# lcd20x4_keyboard.net
KiCad netlist of a schematic drawn in EAGLE
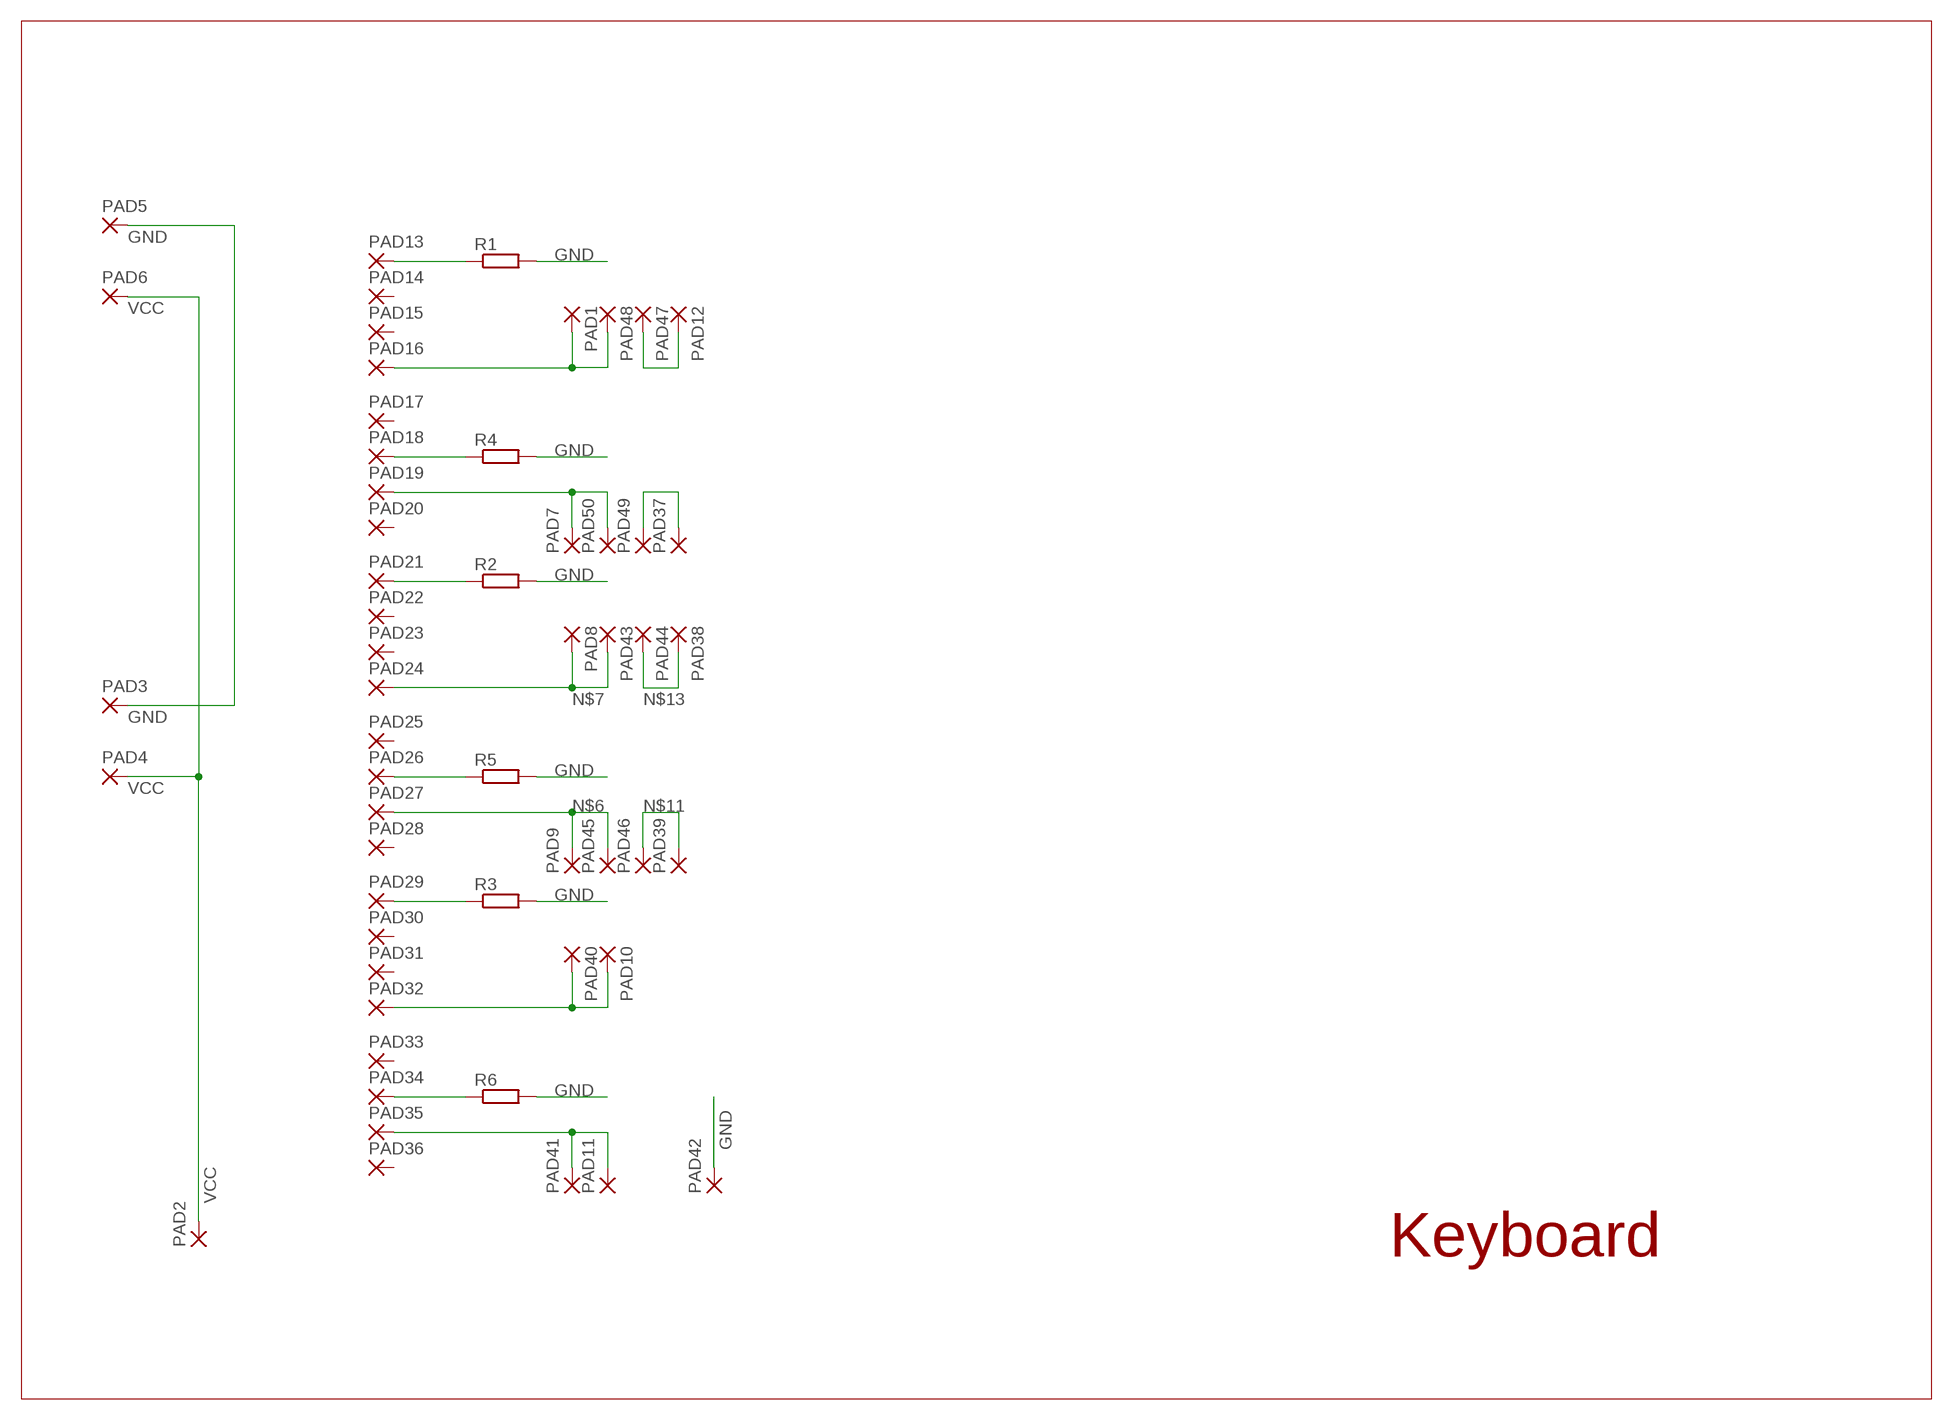
[diagram p0: schematic, sheet 1]

(export (version "E")
  (design (tool "Eeschema 10.0.6"))
  (components
    (comp (ref "PAD1")
      (value "WIREPAD1,6/0,8")
      (footprint "eagle-import:1,6_0,8")
      (libsource (lib "eagle-import") (part "WIREPAD1,6/0,8"))
    )
    (comp (ref "PAD2")
      (value "WIREPAD1,6/0,8")
      (footprint "eagle-import:1,6_0,8")
      (libsource (lib "eagle-import") (part "WIREPAD1,6/0,8"))
    )
    (comp (ref "PAD3")
      (value "WIREPAD1,6/0,8")
      (footprint "eagle-import:1,6_0,8")
      (libsource (lib "eagle-import") (part "WIREPAD1,6/0,8"))
    )
    (comp (ref "PAD4")
      (value "WIREPAD1,6/0,8")
      (footprint "eagle-import:1,6_0,8")
      (libsource (lib "eagle-import") (part "WIREPAD1,6/0,8"))
    )
    (comp (ref "PAD5")
      (value "WIREPAD1,6/0,8")
      (footprint "eagle-import:1,6_0,8")
      (libsource (lib "eagle-import") (part "WIREPAD1,6/0,8"))
    )
    (comp (ref "PAD6")
      (value "WIREPAD1,6/0,8")
      (footprint "eagle-import:1,6_0,8")
      (libsource (lib "eagle-import") (part "WIREPAD1,6/0,8"))
    )
    (comp (ref "PAD7")
      (value "WIREPAD1,6/0,8")
      (footprint "eagle-import:1,6_0,8")
      (libsource (lib "eagle-import") (part "WIREPAD1,6/0,8"))
    )
    (comp (ref "PAD8")
      (value "WIREPAD1,6/0,8")
      (footprint "eagle-import:1,6_0,8")
      (libsource (lib "eagle-import") (part "WIREPAD1,6/0,8"))
    )
    (comp (ref "PAD9")
      (value "WIREPAD1,6/0,8")
      (footprint "eagle-import:1,6_0,8")
      (libsource (lib "eagle-import") (part "WIREPAD1,6/0,8"))
    )
    (comp (ref "PAD10")
      (value "WIREPAD1,6/0,8")
      (footprint "eagle-import:1,6_0,8")
      (libsource (lib "eagle-import") (part "WIREPAD1,6/0,8"))
    )
    (comp (ref "PAD11")
      (value "WIREPAD1,6/0,8")
      (footprint "eagle-import:1,6_0,8")
      (libsource (lib "eagle-import") (part "WIREPAD1,6/0,8"))
    )
    (comp (ref "PAD12")
      (value "WIREPAD1,6/0,8")
      (footprint "eagle-import:1,6_0,8")
      (libsource (lib "eagle-import") (part "WIREPAD1,6/0,8"))
    )
    (comp (ref "PAD13")
      (value "WIREPAD1,6/0,8")
      (footprint "eagle-import:1,6_0,8")
      (libsource (lib "eagle-import") (part "WIREPAD1,6/0,8"))
    )
    (comp (ref "PAD14")
      (value "WIREPAD1,6/0,8")
      (footprint "eagle-import:1,6_0,8")
      (libsource (lib "eagle-import") (part "WIREPAD1,6/0,8"))
    )
    (comp (ref "PAD15")
      (value "WIREPAD1,6/0,8")
      (footprint "eagle-import:1,6_0,8")
      (libsource (lib "eagle-import") (part "WIREPAD1,6/0,8"))
    )
    (comp (ref "PAD16")
      (value "WIREPAD1,6/0,8")
      (footprint "eagle-import:1,6_0,8")
      (libsource (lib "eagle-import") (part "WIREPAD1,6/0,8"))
    )
    (comp (ref "PAD17")
      (value "WIREPAD1,6/0,8")
      (footprint "eagle-import:1,6_0,8")
      (libsource (lib "eagle-import") (part "WIREPAD1,6/0,8"))
    )
    (comp (ref "PAD18")
      (value "WIREPAD1,6/0,8")
      (footprint "eagle-import:1,6_0,8")
      (libsource (lib "eagle-import") (part "WIREPAD1,6/0,8"))
    )
    (comp (ref "PAD19")
      (value "WIREPAD1,6/0,8")
      (footprint "eagle-import:1,6_0,8")
      (libsource (lib "eagle-import") (part "WIREPAD1,6/0,8"))
    )
    (comp (ref "PAD20")
      (value "WIREPAD1,6/0,8")
      (footprint "eagle-import:1,6_0,8")
      (libsource (lib "eagle-import") (part "WIREPAD1,6/0,8"))
    )
    (comp (ref "PAD21")
      (value "WIREPAD1,6/0,8")
      (footprint "eagle-import:1,6_0,8")
      (libsource (lib "eagle-import") (part "WIREPAD1,6/0,8"))
    )
    (comp (ref "PAD22")
      (value "WIREPAD1,6/0,8")
      (footprint "eagle-import:1,6_0,8")
      (libsource (lib "eagle-import") (part "WIREPAD1,6/0,8"))
    )
    (comp (ref "PAD23")
      (value "WIREPAD1,6/0,8")
      (footprint "eagle-import:1,6_0,8")
      (libsource (lib "eagle-import") (part "WIREPAD1,6/0,8"))
    )
    (comp (ref "PAD24")
      (value "WIREPAD1,6/0,8")
      (footprint "eagle-import:1,6_0,8")
      (libsource (lib "eagle-import") (part "WIREPAD1,6/0,8"))
    )
    (comp (ref "PAD25")
      (value "WIREPAD1,6/0,8")
      (footprint "eagle-import:1,6_0,8")
      (libsource (lib "eagle-import") (part "WIREPAD1,6/0,8"))
    )
    (comp (ref "PAD26")
      (value "WIREPAD1,6/0,8")
      (footprint "eagle-import:1,6_0,8")
      (libsource (lib "eagle-import") (part "WIREPAD1,6/0,8"))
    )
    (comp (ref "PAD27")
      (value "WIREPAD1,6/0,8")
      (footprint "eagle-import:1,6_0,8")
      (libsource (lib "eagle-import") (part "WIREPAD1,6/0,8"))
    )
    (comp (ref "PAD28")
      (value "WIREPAD1,6/0,8")
      (footprint "eagle-import:1,6_0,8")
      (libsource (lib "eagle-import") (part "WIREPAD1,6/0,8"))
    )
    (comp (ref "PAD29")
      (value "WIREPAD1,6/0,8")
      (footprint "eagle-import:1,6_0,8")
      (libsource (lib "eagle-import") (part "WIREPAD1,6/0,8"))
    )
    (comp (ref "PAD30")
      (value "WIREPAD1,6/0,8")
      (footprint "eagle-import:1,6_0,8")
      (libsource (lib "eagle-import") (part "WIREPAD1,6/0,8"))
    )
    (comp (ref "PAD31")
      (value "WIREPAD1,6/0,8")
      (footprint "eagle-import:1,6_0,8")
      (libsource (lib "eagle-import") (part "WIREPAD1,6/0,8"))
    )
    (comp (ref "PAD32")
      (value "WIREPAD1,6/0,8")
      (footprint "eagle-import:1,6_0,8")
      (libsource (lib "eagle-import") (part "WIREPAD1,6/0,8"))
    )
    (comp (ref "PAD33")
      (value "WIREPAD1,6/0,8")
      (footprint "eagle-import:1,6_0,8")
      (libsource (lib "eagle-import") (part "WIREPAD1,6/0,8"))
    )
    (comp (ref "PAD34")
      (value "WIREPAD1,6/0,8")
      (footprint "eagle-import:1,6_0,8")
      (libsource (lib "eagle-import") (part "WIREPAD1,6/0,8"))
    )
    (comp (ref "PAD35")
      (value "WIREPAD1,6/0,8")
      (footprint "eagle-import:1,6_0,8")
      (libsource (lib "eagle-import") (part "WIREPAD1,6/0,8"))
    )
    (comp (ref "PAD36")
      (value "WIREPAD1,6/0,8")
      (footprint "eagle-import:1,6_0,8")
      (libsource (lib "eagle-import") (part "WIREPAD1,6/0,8"))
    )
    (comp (ref "PAD37")
      (value "WIREPAD1,6/0,8")
      (footprint "eagle-import:1,6_0,8")
      (libsource (lib "eagle-import") (part "WIREPAD1,6/0,8"))
    )
    (comp (ref "PAD38")
      (value "WIREPAD1,6/0,8")
      (footprint "eagle-import:1,6_0,8")
      (libsource (lib "eagle-import") (part "WIREPAD1,6/0,8"))
    )
    (comp (ref "PAD39")
      (value "WIREPAD1,6/0,8")
      (footprint "eagle-import:1,6_0,8")
      (libsource (lib "eagle-import") (part "WIREPAD1,6/0,8"))
    )
    (comp (ref "PAD40")
      (value "WIREPAD1,6/0,8")
      (footprint "eagle-import:1,6_0,8")
      (libsource (lib "eagle-import") (part "WIREPAD1,6/0,8"))
    )
    (comp (ref "PAD41")
      (value "WIREPAD1,6/0,8")
      (footprint "eagle-import:1,6_0,8")
      (libsource (lib "eagle-import") (part "WIREPAD1,6/0,8"))
    )
    (comp (ref "PAD42")
      (value "WIREPAD1,6/0,8")
      (footprint "eagle-import:1,6_0,8")
      (libsource (lib "eagle-import") (part "WIREPAD1,6/0,8"))
    )
    (comp (ref "PAD43")
      (value "WIREPAD1,6/0,8")
      (footprint "eagle-import:1,6_0,8")
      (libsource (lib "eagle-import") (part "WIREPAD1,6/0,8"))
    )
    (comp (ref "PAD44")
      (value "WIREPAD1,6/0,8")
      (footprint "eagle-import:1,6_0,8")
      (libsource (lib "eagle-import") (part "WIREPAD1,6/0,8"))
    )
    (comp (ref "PAD45")
      (value "WIREPAD1,6/0,8")
      (footprint "eagle-import:1,6_0,8")
      (libsource (lib "eagle-import") (part "WIREPAD1,6/0,8"))
    )
    (comp (ref "PAD46")
      (value "WIREPAD1,6/0,8")
      (footprint "eagle-import:1,6_0,8")
      (libsource (lib "eagle-import") (part "WIREPAD1,6/0,8"))
    )
    (comp (ref "PAD47")
      (value "WIREPAD1,6/0,8")
      (footprint "eagle-import:1,6_0,8")
      (libsource (lib "eagle-import") (part "WIREPAD1,6/0,8"))
    )
    (comp (ref "PAD48")
      (value "WIREPAD1,6/0,8")
      (footprint "eagle-import:1,6_0,8")
      (libsource (lib "eagle-import") (part "WIREPAD1,6/0,8"))
    )
    (comp (ref "PAD49")
      (value "WIREPAD1,6/0,8")
      (footprint "eagle-import:1,6_0,8")
      (libsource (lib "eagle-import") (part "WIREPAD1,6/0,8"))
    )
    (comp (ref "PAD50")
      (value "WIREPAD1,6/0,8")
      (footprint "eagle-import:1,6_0,8")
      (libsource (lib "eagle-import") (part "WIREPAD1,6/0,8"))
    )
    (comp (ref "R1")
      (value "R-EU_M0805")
      (footprint "eagle-import:M0805")
      (libsource (lib "eagle-import") (part "R-EU_M0805"))
    )
    (comp (ref "R2")
      (value "R-EU_M0805")
      (footprint "eagle-import:M0805")
      (libsource (lib "eagle-import") (part "R-EU_M0805"))
    )
    (comp (ref "R3")
      (value "R-EU_M0805")
      (footprint "eagle-import:M0805")
      (libsource (lib "eagle-import") (part "R-EU_M0805"))
    )
    (comp (ref "R4")
      (value "R-EU_M0805")
      (footprint "eagle-import:M0805")
      (libsource (lib "eagle-import") (part "R-EU_M0805"))
    )
    (comp (ref "R5")
      (value "R-EU_M0805")
      (footprint "eagle-import:M0805")
      (libsource (lib "eagle-import") (part "R-EU_M0805"))
    )
    (comp (ref "R6")
      (value "R-EU_M0805")
      (footprint "eagle-import:M0805")
      (libsource (lib "eagle-import") (part "R-EU_M0805"))
    )
  )
  (nets
    (net (code "1") (name "/GND") (class "Default")
      (node (ref "PAD3") (pin "1") (pinfunction "P_1") (pintype "passive"))
      (node (ref "PAD42") (pin "1") (pinfunction "P_1") (pintype "passive"))
      (node (ref "PAD5") (pin "1") (pinfunction "P_1") (pintype "passive"))
      (node (ref "R1") (pin "2") (pinfunction "2_2") (pintype "passive"))
      (node (ref "R2") (pin "2") (pinfunction "2_2") (pintype "passive"))
      (node (ref "R3") (pin "2") (pinfunction "2_2") (pintype "passive"))
      (node (ref "R4") (pin "2") (pinfunction "2_2") (pintype "passive"))
      (node (ref "R5") (pin "2") (pinfunction "2_2") (pintype "passive"))
      (node (ref "R6") (pin "2") (pinfunction "2_2") (pintype "passive"))
    )
    (net (code "2") (name "/N$6") (class "Default")
      (node (ref "PAD27") (pin "1") (pinfunction "P_1") (pintype "passive"))
      (node (ref "PAD45") (pin "1") (pinfunction "P_1") (pintype "passive"))
      (node (ref "PAD9") (pin "1") (pinfunction "P_1") (pintype "passive"))
    )
    (net (code "3") (name "/N$7") (class "Default")
      (node (ref "PAD24") (pin "1") (pinfunction "P_1") (pintype "passive"))
      (node (ref "PAD43") (pin "1") (pinfunction "P_1") (pintype "passive"))
      (node (ref "PAD8") (pin "1") (pinfunction "P_1") (pintype "passive"))
    )
    (net (code "4") (name "/N$11") (class "Default")
      (node (ref "PAD39") (pin "1") (pinfunction "P_1") (pintype "passive"))
      (node (ref "PAD46") (pin "1") (pinfunction "P_1") (pintype "passive"))
    )
    (net (code "5") (name "/N$13") (class "Default")
      (node (ref "PAD38") (pin "1") (pinfunction "P_1") (pintype "passive"))
      (node (ref "PAD44") (pin "1") (pinfunction "P_1") (pintype "passive"))
    )
    (net (code "6") (name "/VCC") (class "Default")
      (node (ref "PAD2") (pin "1") (pinfunction "P_1") (pintype "passive"))
      (node (ref "PAD4") (pin "1") (pinfunction "P_1") (pintype "passive"))
      (node (ref "PAD6") (pin "1") (pinfunction "P_1") (pintype "passive"))
    )
    (net (code "7") (name "Net-(PAD1-P)") (class "Default")
      (node (ref "PAD1") (pin "1") (pinfunction "P_1") (pintype "passive"))
      (node (ref "PAD16") (pin "1") (pinfunction "P_1") (pintype "passive"))
      (node (ref "PAD48") (pin "1") (pinfunction "P_1") (pintype "passive"))
    )
    (net (code "8") (name "Net-(PAD10-P)") (class "Default")
      (node (ref "PAD10") (pin "1") (pinfunction "P_1") (pintype "passive"))
      (node (ref "PAD32") (pin "1") (pinfunction "P_1") (pintype "passive"))
      (node (ref "PAD40") (pin "1") (pinfunction "P_1") (pintype "passive"))
    )
    (net (code "9") (name "Net-(PAD11-P)") (class "Default")
      (node (ref "PAD11") (pin "1") (pinfunction "P_1") (pintype "passive"))
      (node (ref "PAD35") (pin "1") (pinfunction "P_1") (pintype "passive"))
      (node (ref "PAD41") (pin "1") (pinfunction "P_1") (pintype "passive"))
    )
    (net (code "10") (name "Net-(PAD12-P)") (class "Default")
      (node (ref "PAD12") (pin "1") (pinfunction "P_1") (pintype "passive"))
      (node (ref "PAD47") (pin "1") (pinfunction "P_1") (pintype "passive"))
    )
    (net (code "11") (name "Net-(PAD13-P)") (class "Default")
      (node (ref "PAD13") (pin "1") (pinfunction "P_1") (pintype "passive"))
      (node (ref "R1") (pin "1") (pinfunction "1_1") (pintype "passive"))
    )
    (net (code "12") (name "Net-(PAD18-P)") (class "Default")
      (node (ref "PAD18") (pin "1") (pinfunction "P_1") (pintype "passive"))
      (node (ref "R4") (pin "1") (pinfunction "1_1") (pintype "passive"))
    )
    (net (code "13") (name "Net-(PAD19-P)") (class "Default")
      (node (ref "PAD19") (pin "1") (pinfunction "P_1") (pintype "passive"))
      (node (ref "PAD50") (pin "1") (pinfunction "P_1") (pintype "passive"))
      (node (ref "PAD7") (pin "1") (pinfunction "P_1") (pintype "passive"))
    )
    (net (code "14") (name "Net-(PAD21-P)") (class "Default")
      (node (ref "PAD21") (pin "1") (pinfunction "P_1") (pintype "passive"))
      (node (ref "R2") (pin "1") (pinfunction "1_1") (pintype "passive"))
    )
    (net (code "15") (name "Net-(PAD26-P)") (class "Default")
      (node (ref "PAD26") (pin "1") (pinfunction "P_1") (pintype "passive"))
      (node (ref "R5") (pin "1") (pinfunction "1_1") (pintype "passive"))
    )
    (net (code "16") (name "Net-(PAD29-P)") (class "Default")
      (node (ref "PAD29") (pin "1") (pinfunction "P_1") (pintype "passive"))
      (node (ref "R3") (pin "1") (pinfunction "1_1") (pintype "passive"))
    )
    (net (code "17") (name "Net-(PAD34-P)") (class "Default")
      (node (ref "PAD34") (pin "1") (pinfunction "P_1") (pintype "passive"))
      (node (ref "R6") (pin "1") (pinfunction "1_1") (pintype "passive"))
    )
    (net (code "18") (name "Net-(PAD37-P)") (class "Default")
      (node (ref "PAD37") (pin "1") (pinfunction "P_1") (pintype "passive"))
      (node (ref "PAD49") (pin "1") (pinfunction "P_1") (pintype "passive"))
    )
    (net (code "19") (name "unconnected-(PAD14-P-Pad1)") (class "Default")
      (node (ref "PAD14") (pin "1") (pinfunction "P_1") (pintype "passive"))
    )
    (net (code "20") (name "unconnected-(PAD15-P-Pad1)") (class "Default")
      (node (ref "PAD15") (pin "1") (pinfunction "P_1") (pintype "passive"))
    )
    (net (code "21") (name "unconnected-(PAD17-P-Pad1)") (class "Default")
      (node (ref "PAD17") (pin "1") (pinfunction "P_1") (pintype "passive"))
    )
    (net (code "22") (name "unconnected-(PAD20-P-Pad1)") (class "Default")
      (node (ref "PAD20") (pin "1") (pinfunction "P_1") (pintype "passive"))
    )
    (net (code "23") (name "unconnected-(PAD22-P-Pad1)") (class "Default")
      (node (ref "PAD22") (pin "1") (pinfunction "P_1") (pintype "passive"))
    )
    (net (code "24") (name "unconnected-(PAD23-P-Pad1)") (class "Default")
      (node (ref "PAD23") (pin "1") (pinfunction "P_1") (pintype "passive"))
    )
    (net (code "25") (name "unconnected-(PAD25-P-Pad1)") (class "Default")
      (node (ref "PAD25") (pin "1") (pinfunction "P_1") (pintype "passive"))
    )
    (net (code "26") (name "unconnected-(PAD28-P-Pad1)") (class "Default")
      (node (ref "PAD28") (pin "1") (pinfunction "P_1") (pintype "passive"))
    )
    (net (code "27") (name "unconnected-(PAD30-P-Pad1)") (class "Default")
      (node (ref "PAD30") (pin "1") (pinfunction "P_1") (pintype "passive"))
    )
    (net (code "28") (name "unconnected-(PAD31-P-Pad1)") (class "Default")
      (node (ref "PAD31") (pin "1") (pinfunction "P_1") (pintype "passive"))
    )
    (net (code "29") (name "unconnected-(PAD33-P-Pad1)") (class "Default")
      (node (ref "PAD33") (pin "1") (pinfunction "P_1") (pintype "passive"))
    )
    (net (code "30") (name "unconnected-(PAD36-P-Pad1)") (class "Default")
      (node (ref "PAD36") (pin "1") (pinfunction "P_1") (pintype "passive"))
    )
  )
)
